# motor_sensor.net
KiCad netlist of a schematic drawn in Altium Designer
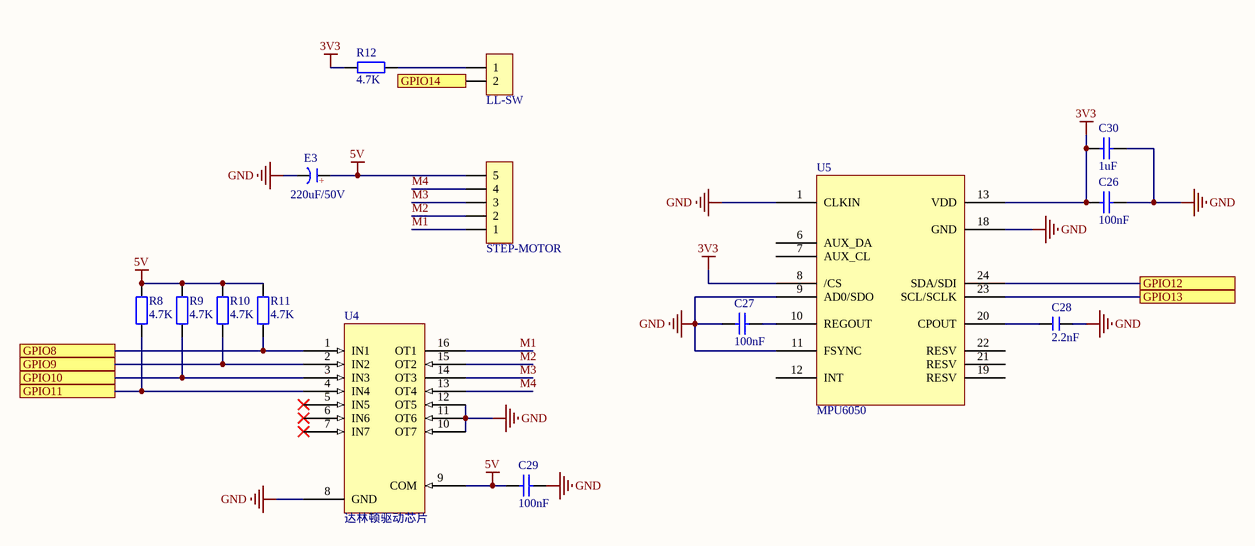
[diagram p0: motor&sensor.SchDoc]

(export (version "E")
  (design (tool "Eeschema 10.0.6"))
  (components
    (comp (ref "C26")
      (value "100nF")
      (footprint "C 0603_L")
      (description "贴片电容")
      (libsource (lib "0.1 - 电阻-电容-电感") (part "C"))
    )
    (comp (ref "C27")
      (value "100nF")
      (footprint "C 0603_L")
      (description "贴片电容")
      (libsource (lib "0.1 - 电阻-电容-电感") (part "C"))
    )
    (comp (ref "C28")
      (value "2.2nF")
      (footprint "C 0603_L")
      (description "贴片电容")
      (libsource (lib "") (part "C_1"))
    )
    (comp (ref "C29")
      (value "100nF")
      (footprint "C 0603_L")
      (description "贴片电容")
      (libsource (lib "0.1 - 电阻-电容-电感") (part "C"))
    )
    (comp (ref "C30")
      (value "1uF")
      (footprint "C 0603_L")
      (description "贴片电容")
      (libsource (lib "0.1 - 电阻-电容-电感") (part "C"))
    )
    (comp (ref "E3")
      (value "220uF/50V")
      (footprint "CT 10*8 - C")
      (description "贴片固态电容")
      (libsource (lib "0.1 - 电阻-电容-电感") (part "CS_SMD"))
    )
    (comp (ref "LL-SW")
      (value "HDR-1X2")
      (footprint "XH2.54-WI-2P")
      (description "2P接插件")
      (libsource (lib "5.4 - 接插件-脚距2.54 (100mil) ") (part "Header 2"))
    )
    (comp (ref "R8")
      (value "4.7K")
      (footprint "R 0603_L")
      (description "贴片电阻")
      (libsource (lib "0.1 - 电阻-电容-电感") (part "R"))
    )
    (comp (ref "R9")
      (value "4.7K")
      (footprint "R 0603_L")
      (description "贴片电阻")
      (libsource (lib "0.1 - 电阻-电容-电感") (part "R"))
    )
    (comp (ref "R10")
      (value "4.7K")
      (footprint "R 0603_L")
      (description "贴片电阻")
      (libsource (lib "0.1 - 电阻-电容-电感") (part "R"))
    )
    (comp (ref "R11")
      (value "4.7K")
      (footprint "R 0603_L")
      (description "贴片电阻")
      (libsource (lib "0.1 - 电阻-电容-电感") (part "R"))
    )
    (comp (ref "R12")
      (value "4.7K")
      (footprint "R 0603_L")
      (description "贴片电阻")
      (libsource (lib "0.1 - 电阻-电容-电感") (part "R"))
    )
    (comp (ref "STEP-MOTOR")
      (value "HDR-1X5")
      (footprint "XH2.54-WI-5P")
      (description "5P接插件")
      (libsource (lib "5.4 - 接插件-脚距2.54 (100mil) ") (part "Header 5"))
    )
    (comp (ref "U4") (value "达林顿驱动芯片") (footprint "SOP16") (libsource (lib "1.1 - 常见芯片") (part "ULN2003")))
    (comp (ref "U5")
      (value "MPU6050")
      (footprint "QFN24 4x4_N")
      (description "三轴加速度计和三轴陀螺仪，工作电压：2.375V~3.46V")
      (libsource (lib "8.1 - 传感器") (part "MPU6050"))
    )
  )
  (nets
    (net (code "1") (name "/GPIO8") (class "Default")
      (node (ref "R11") (pin "1") (pinfunction "1_1") (pintype "passive"))
      (node (ref "U4") (pin "1") (pinfunction "IN1_1") (pintype "input"))
    )
    (net (code "2") (name "/GPIO9") (class "Default")
      (node (ref "R10") (pin "1") (pinfunction "1_1") (pintype "passive"))
      (node (ref "U4") (pin "2") (pinfunction "IN2_2") (pintype "input"))
    )
    (net (code "3") (name "/GPIO10") (class "Default")
      (node (ref "R9") (pin "1") (pinfunction "1_1") (pintype "passive"))
      (node (ref "U4") (pin "3") (pinfunction "IN3_3") (pintype "input"))
    )
    (net (code "4") (name "/GPIO11") (class "Default")
      (node (ref "R8") (pin "1") (pinfunction "1_1") (pintype "passive"))
      (node (ref "U4") (pin "4") (pinfunction "IN4_4") (pintype "input"))
    )
    (net (code "5") (name "/GPIO12") (class "Default")
      (node (ref "U5") (pin "24") (pinfunction "SDA/SDI_24") (pintype "passive"))
    )
    (net (code "6") (name "/GPIO13") (class "Default")
      (node (ref "U5") (pin "23") (pinfunction "SCL/SCLK_23") (pintype "passive"))
    )
    (net (code "7") (name "/GPIO14") (class "Default")
      (node (ref "LL-SW") (pin "2") (pinfunction "2_2") (pintype "passive"))
    )
    (net (code "8") (name "/M1") (class "Default")
      (node (ref "STEP-MOTOR") (pin "1") (pinfunction "1_1") (pintype "passive"))
      (node (ref "U4") (pin "16") (pinfunction "OT1_16") (pintype "power_in"))
    )
    (net (code "9") (name "/M2") (class "Default")
      (node (ref "STEP-MOTOR") (pin "2") (pinfunction "2_2") (pintype "passive"))
      (node (ref "U4") (pin "15") (pinfunction "OT2_15") (pintype "input"))
    )
    (net (code "10") (name "/M3") (class "Default")
      (node (ref "STEP-MOTOR") (pin "3") (pinfunction "3_3") (pintype "passive"))
      (node (ref "U4") (pin "14") (pinfunction "OT3_14") (pintype "tri_state"))
    )
    (net (code "11") (name "/M4") (class "Default")
      (node (ref "STEP-MOTOR") (pin "4") (pinfunction "4_4") (pintype "passive"))
      (node (ref "U4") (pin "13") (pinfunction "OT4_13") (pintype "input"))
    )
    (net (code "12") (name "3V3") (class "Default")
      (node (ref "C26") (pin "1") (pinfunction "1_1") (pintype "passive"))
      (node (ref "C30") (pin "1") (pinfunction "1_1") (pintype "passive"))
      (node (ref "R12") (pin "2") (pinfunction "2_2") (pintype "passive"))
      (node (ref "U5") (pin "13") (pinfunction "VDD_13") (pintype "passive"))
      (node (ref "U5") (pin "8") (pinfunction "/CS_8") (pintype "passive"))
    )
    (net (code "13") (name "5V") (class "Default")
      (node (ref "C29") (pin "1") (pinfunction "1_1") (pintype "passive"))
      (node (ref "E3") (pin "1") (pinfunction "A_1") (pintype "passive"))
      (node (ref "R10") (pin "2") (pinfunction "2_2") (pintype "passive"))
      (node (ref "R11") (pin "2") (pinfunction "2_2") (pintype "passive"))
      (node (ref "R8") (pin "2") (pinfunction "2_2") (pintype "passive"))
      (node (ref "R9") (pin "2") (pinfunction "2_2") (pintype "passive"))
      (node (ref "STEP-MOTOR") (pin "5") (pinfunction "5_5") (pintype "passive"))
      (node (ref "U4") (pin "9") (pinfunction "COM_9") (pintype "input"))
    )
    (net (code "14") (name "GND") (class "Default")
      (node (ref "C26") (pin "2") (pinfunction "2_2") (pintype "passive"))
      (node (ref "C27") (pin "1") (pinfunction "1_1") (pintype "passive"))
      (node (ref "C28") (pin "1") (pinfunction "1_1") (pintype "passive"))
      (node (ref "C29") (pin "2") (pinfunction "2_2") (pintype "passive"))
      (node (ref "C30") (pin "2") (pinfunction "2_2") (pintype "passive"))
      (node (ref "E3") (pin "2") (pinfunction "K_2") (pintype "passive"))
      (node (ref "U4") (pin "10") (pinfunction "OT7_10") (pintype "input"))
      (node (ref "U4") (pin "11") (pinfunction "OT6_11") (pintype "input"))
      (node (ref "U4") (pin "12") (pinfunction "OT5_12") (pintype "input"))
      (node (ref "U4") (pin "8") (pinfunction "GND_8") (pintype "power_in"))
      (node (ref "U5") (pin "1") (pinfunction "CLKIN_1") (pintype "passive"))
      (node (ref "U5") (pin "11") (pinfunction "FSYNC_11") (pintype "passive"))
      (node (ref "U5") (pin "18") (pinfunction "GND_18") (pintype "passive"))
      (node (ref "U5") (pin "9") (pinfunction "AD0/SDO_9") (pintype "passive"))
    )
    (net (code "15") (name "Net-(LL-SW-Pad1)") (class "Default")
      (node (ref "LL-SW") (pin "1") (pinfunction "1_1") (pintype "passive"))
      (node (ref "R12") (pin "1") (pinfunction "1_1") (pintype "passive"))
    )
    (net (code "16") (name "Net-(U5-CPOUT)") (class "Default")
      (node (ref "C28") (pin "2") (pinfunction "2_2") (pintype "passive"))
      (node (ref "U5") (pin "20") (pinfunction "CPOUT_20") (pintype "passive"))
    )
    (net (code "17") (name "Net-(U5-REGOUT)") (class "Default")
      (node (ref "C27") (pin "2") (pinfunction "2_2") (pintype "passive"))
      (node (ref "U5") (pin "10") (pinfunction "REGOUT_10") (pintype "passive"))
    )
    (net (code "18") (name "unconnected-(U4-IN5-Pad5)") (class "Default")
      (node (ref "U4") (pin "5") (pinfunction "IN5_5") (pintype "input+no_connect"))
    )
    (net (code "19") (name "unconnected-(U4-IN6-Pad6)") (class "Default")
      (node (ref "U4") (pin "6") (pinfunction "IN6_6") (pintype "input+no_connect"))
    )
    (net (code "20") (name "unconnected-(U4-IN7-Pad7)") (class "Default")
      (node (ref "U4") (pin "7") (pinfunction "IN7_7") (pintype "input+no_connect"))
    )
    (net (code "21") (name "unconnected-(U5-AUX_CL-Pad7)") (class "Default")
      (node (ref "U5") (pin "7") (pinfunction "AUX_CL_7") (pintype "passive"))
    )
    (net (code "22") (name "unconnected-(U5-AUX_DA-Pad6)") (class "Default")
      (node (ref "U5") (pin "6") (pinfunction "AUX_DA_6") (pintype "passive"))
    )
    (net (code "23") (name "unconnected-(U5-INT-Pad12)") (class "Default")
      (node (ref "U5") (pin "12") (pinfunction "INT_12") (pintype "passive"))
    )
    (net (code "24") (name "unconnected-(U5-RESV-Pad19)") (class "Default")
      (node (ref "U5") (pin "19") (pinfunction "RESV_19") (pintype "passive"))
    )
    (net (code "25") (name "unconnected-(U5-RESV-Pad21)") (class "Default")
      (node (ref "U5") (pin "21") (pinfunction "RESV_21") (pintype "passive"))
    )
    (net (code "26") (name "unconnected-(U5-RESV-Pad22)") (class "Default")
      (node (ref "U5") (pin "22") (pinfunction "RESV_22") (pintype "passive"))
    )
  )
)
